# ESP-WROOM32-Breakout_v13.net
KiCad netlist of a schematic drawn in EAGLE
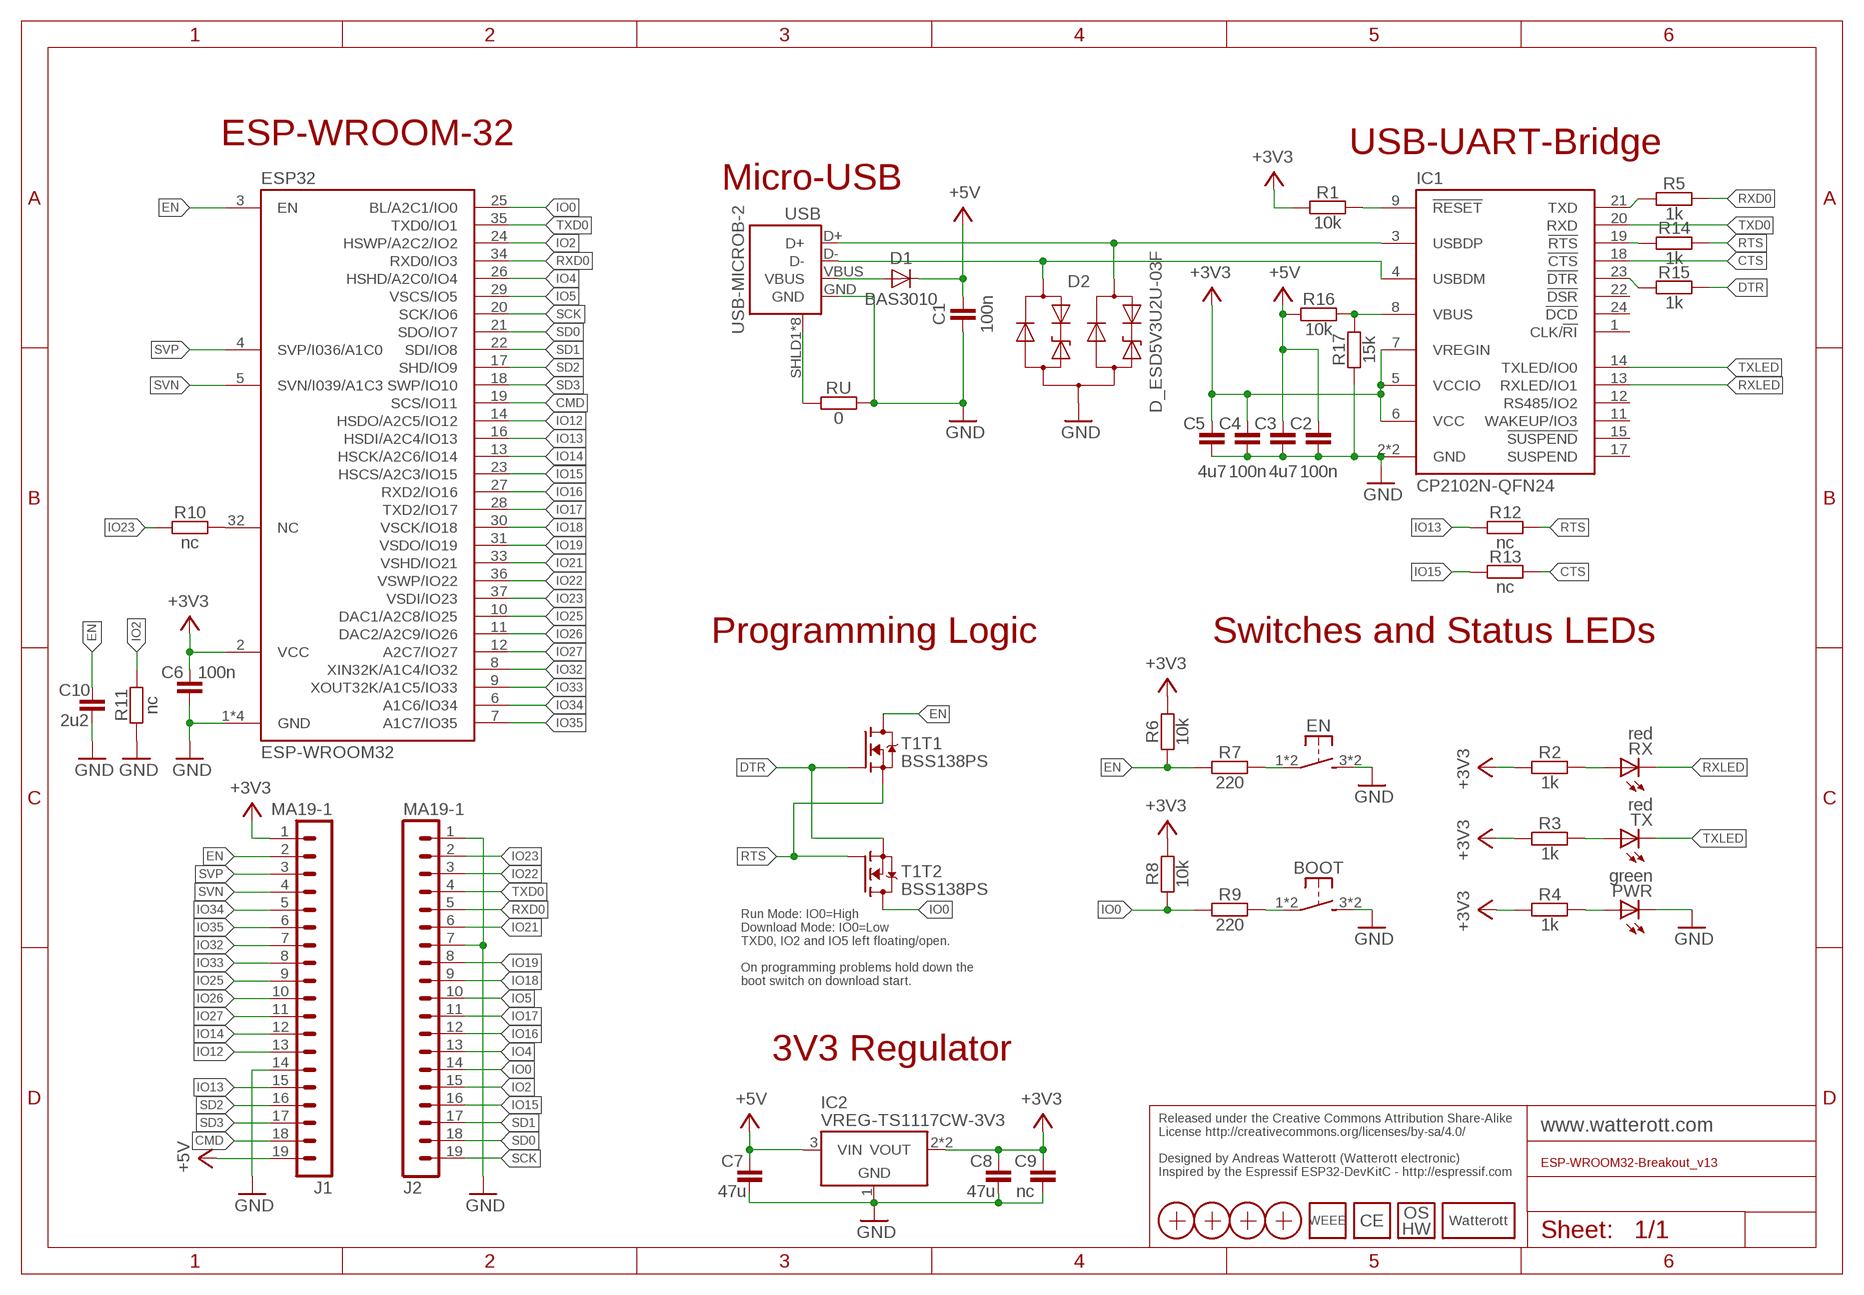
[diagram p0: schematic, sheet 1]

(export (version "E")
  (design (tool "Eeschema 10.0.6"))
  (components
    (comp (ref "BOOT")
      (value "SW-TACTILE-PTS840P")
      (footprint "eagle-import:PTS840P")
      (libsource (lib "eagle-import") (part "SW-TACTILE-PTS840P"))
    )
    (comp (ref "C1")
      (value "100n")
      (footprint "eagle-import:C0402")
      (libsource (lib "eagle-import") (part "CAPACITOR-0402"))
    )
    (comp (ref "C2")
      (value "100n")
      (footprint "eagle-import:C0402")
      (libsource (lib "eagle-import") (part "CAPACITOR-0402"))
    )
    (comp (ref "C3")
      (value "4u7")
      (footprint "eagle-import:C0603")
      (libsource (lib "eagle-import") (part "CAPACITOR-0603"))
    )
    (comp (ref "C4")
      (value "100n")
      (footprint "eagle-import:C0402")
      (libsource (lib "eagle-import") (part "CAPACITOR-0402"))
    )
    (comp (ref "C5")
      (value "4u7")
      (footprint "eagle-import:C0603")
      (libsource (lib "eagle-import") (part "CAPACITOR-0603"))
    )
    (comp (ref "C6")
      (value "100n")
      (footprint "eagle-import:C0402")
      (libsource (lib "eagle-import") (part "CAPACITOR-0402"))
    )
    (comp (ref "C7")
      (value "47u")
      (footprint "eagle-import:C1206")
      (libsource (lib "eagle-import") (part "CAPACITOR-1206"))
    )
    (comp (ref "C8")
      (value "47u")
      (footprint "eagle-import:C1206")
      (libsource (lib "eagle-import") (part "CAPACITOR-1206"))
    )
    (comp (ref "C9")
      (value "nc")
      (footprint "eagle-import:C1206")
      (libsource (lib "eagle-import") (part "CAPACITOR-1206"))
    )
    (comp (ref "C10")
      (value "2u2")
      (footprint "eagle-import:C0402")
      (libsource (lib "eagle-import") (part "CAPACITOR-0402"))
    )
    (comp (ref "D1")
      (value "BAS3010")
      (footprint "eagle-import:SOD323")
      (libsource (lib "eagle-import") (part "DIODE-SOD323"))
    )
    (comp (ref "D2")
      (value "D_ESD5V3U2U-03F")
      (footprint "eagle-import:SOT723")
      (libsource (lib "eagle-import") (part "D_ESD5V3U2U-03F"))
    )
    (comp (ref "EN")
      (value "SW-TACTILE-PTS840P")
      (footprint "eagle-import:PTS840P")
      (libsource (lib "eagle-import") (part "SW-TACTILE-PTS840P"))
    )
    (comp (ref "ESP32")
      (value "ESP-WROOM32")
      (footprint "eagle-import:ESP-WROOM32")
      (libsource (lib "eagle-import") (part "ESP-WROOM32"))
    )
    (comp (ref "IC1")
      (value "CP2102N-QFN24")
      (footprint "eagle-import:QFN24-PAD")
      (libsource (lib "eagle-import") (part "CP2102N-QFN24"))
    )
    (comp (ref "IC2")
      (value "VREG-TS1117CW-3V3")
      (footprint "eagle-import:SOT223")
      (libsource (lib "eagle-import") (part "VREG-TS1117CW-3V3"))
    )
    (comp (ref "J1")
      (value "MA19-1")
      (footprint "eagle-import:MA19-1")
      (libsource (lib "eagle-import") (part "MA19-1"))
    )
    (comp (ref "J2")
      (value "MA19-1")
      (footprint "eagle-import:MA19-1")
      (libsource (lib "eagle-import") (part "MA19-1"))
    )
    (comp (ref "LOGO1")
      (value "LOGO_SPARK-4")
      (footprint "eagle-import:SPARK_4MM")
      (libsource (lib "eagle-import") (part "LOGO_SPARK-4"))
    )
    (comp (ref "LOGO2")
      (value "LOGO_OSHW-2")
      (footprint "eagle-import:OSHW_2MM")
      (libsource (lib "eagle-import") (part "LOGO_OSHW-2"))
    )
    (comp (ref "LOGO3")
      (value "LOGO_CE-2")
      (footprint "eagle-import:CE_2MM")
      (libsource (lib "eagle-import") (part "LOGO_CE-2"))
    )
    (comp (ref "LOGO4")
      (value "LOGO_WEEE-4")
      (footprint "eagle-import:WEEE_4MM")
      (libsource (lib "eagle-import") (part "LOGO_WEEE-4"))
    )
    (comp (ref "PWR")
      (value "green")
      (footprint "eagle-import:C0603")
      (libsource (lib "eagle-import") (part "LED-0603"))
    )
    (comp (ref "R1")
      (value "10k")
      (footprint "eagle-import:C0402")
      (libsource (lib "eagle-import") (part "RESISTOR-0402"))
    )
    (comp (ref "R2")
      (value "1k")
      (footprint "eagle-import:C0402")
      (libsource (lib "eagle-import") (part "RESISTOR-0402"))
    )
    (comp (ref "R3")
      (value "1k")
      (footprint "eagle-import:C0402")
      (libsource (lib "eagle-import") (part "RESISTOR-0402"))
    )
    (comp (ref "R4")
      (value "1k")
      (footprint "eagle-import:C0402")
      (libsource (lib "eagle-import") (part "RESISTOR-0402"))
    )
    (comp (ref "R5")
      (value "1k")
      (footprint "eagle-import:C0402")
      (libsource (lib "eagle-import") (part "RESISTOR-0402"))
    )
    (comp (ref "R6")
      (value "10k")
      (footprint "eagle-import:C0402")
      (libsource (lib "eagle-import") (part "RESISTOR-0402"))
    )
    (comp (ref "R7")
      (value "220")
      (footprint "eagle-import:C0402")
      (libsource (lib "eagle-import") (part "RESISTOR-0402"))
    )
    (comp (ref "R8")
      (value "10k")
      (footprint "eagle-import:C0402")
      (libsource (lib "eagle-import") (part "RESISTOR-0402"))
    )
    (comp (ref "R9")
      (value "220")
      (footprint "eagle-import:C0402")
      (libsource (lib "eagle-import") (part "RESISTOR-0402"))
    )
    (comp (ref "R10")
      (value "nc")
      (footprint "eagle-import:C0402")
      (libsource (lib "eagle-import") (part "RESISTOR-0402"))
    )
    (comp (ref "R11")
      (value "nc")
      (footprint "eagle-import:C0402")
      (libsource (lib "eagle-import") (part "RESISTOR-0402"))
    )
    (comp (ref "R12")
      (value "nc")
      (footprint "eagle-import:C0402")
      (libsource (lib "eagle-import") (part "RESISTOR-0402"))
    )
    (comp (ref "R13")
      (value "nc")
      (footprint "eagle-import:C0402")
      (libsource (lib "eagle-import") (part "RESISTOR-0402"))
    )
    (comp (ref "R14")
      (value "1k")
      (footprint "eagle-import:C0402")
      (libsource (lib "eagle-import") (part "RESISTOR-0402"))
    )
    (comp (ref "R15")
      (value "1k")
      (footprint "eagle-import:C0402")
      (libsource (lib "eagle-import") (part "RESISTOR-0402"))
    )
    (comp (ref "R16")
      (value "10k")
      (footprint "eagle-import:C0402")
      (libsource (lib "eagle-import") (part "RESISTOR-0402"))
    )
    (comp (ref "R17")
      (value "15k")
      (footprint "eagle-import:C0402")
      (libsource (lib "eagle-import") (part "RESISTOR-0402"))
    )
    (comp (ref "RU")
      (value "0")
      (footprint "eagle-import:C0402")
      (libsource (lib "eagle-import") (part "RESISTOR-0402"))
    )
    (comp (ref "RX")
      (value "red")
      (footprint "eagle-import:C0603")
      (libsource (lib "eagle-import") (part "LED-0603"))
    )
    (comp (ref "T1")
      (value "BSS138PS")
      (footprint "eagle-import:SOT363")
      (libsource (lib "eagle-import") (part "BSS138PS"))
    )
    (comp (ref "TX")
      (value "red")
      (footprint "eagle-import:C0603")
      (libsource (lib "eagle-import") (part "LED-0603"))
    )
    (comp (ref "USB")
      (value "USB-MICROB-2")
      (footprint "eagle-import:USB-MICROB-10118194")
      (libsource (lib "eagle-import") (part "USB-MICROB-2"))
    )
    (comp (ref "X1")
      (value "PASSER-07")
      (footprint "eagle-import:PASSER_07MM")
      (libsource (lib "eagle-import") (part "PASSER-07"))
    )
    (comp (ref "X2")
      (value "PASSER-07")
      (footprint "eagle-import:PASSER_07MM")
      (libsource (lib "eagle-import") (part "PASSER-07"))
    )
    (comp (ref "X3")
      (value "PASSER-07")
      (footprint "eagle-import:PASSER_07MM")
      (libsource (lib "eagle-import") (part "PASSER-07"))
    )
    (comp (ref "X4")
      (value "PASSER-07")
      (footprint "eagle-import:PASSER_07MM")
      (libsource (lib "eagle-import") (part "PASSER-07"))
    )
  )
  (nets
    (net (code "1") (name "+3V3") (class "Default")
      (node (ref "C4") (pin "2") (pinfunction "2_2") (pintype "passive"))
      (node (ref "C5") (pin "2") (pinfunction "2_2") (pintype "passive"))
      (node (ref "C6") (pin "2") (pinfunction "2_2") (pintype "passive"))
      (node (ref "C8") (pin "2") (pinfunction "2_2") (pintype "passive"))
      (node (ref "C9") (pin "2") (pinfunction "2_2") (pintype "passive"))
      (node (ref "ESP32") (pin "2") (pinfunction "VCC_2") (pintype "power_in"))
      (node (ref "IC1") (pin "5") (pinfunction "VCCIO_5") (pintype "power_in"))
      (node (ref "IC1") (pin "6") (pinfunction "VCC_6") (pintype "power_in"))
      (node (ref "IC1") (pin "7") (pinfunction "VREGIN_7") (pintype "power_in"))
      (node (ref "IC2") (pin "2") (pinfunction "VOUT_2") (pintype "power_in"))
      (node (ref "IC2") (pin "4") (pinfunction "VOUT_4") (pintype "power_in"))
      (node (ref "J1") (pin "1") (pinfunction "1_1") (pintype "passive"))
      (node (ref "R1") (pin "1") (pinfunction "1_1") (pintype "passive"))
      (node (ref "R2") (pin "1") (pinfunction "1_1") (pintype "passive"))
      (node (ref "R3") (pin "1") (pinfunction "1_1") (pintype "passive"))
      (node (ref "R4") (pin "1") (pinfunction "1_1") (pintype "passive"))
      (node (ref "R6") (pin "2") (pinfunction "2_2") (pintype "passive"))
      (node (ref "R8") (pin "2") (pinfunction "2_2") (pintype "passive"))
    )
    (net (code "2") (name "+5V") (class "Default")
      (node (ref "C1") (pin "2") (pinfunction "2_2") (pintype "passive"))
      (node (ref "C2") (pin "2") (pinfunction "2_2") (pintype "passive"))
      (node (ref "C3") (pin "2") (pinfunction "2_2") (pintype "passive"))
      (node (ref "C7") (pin "2") (pinfunction "2_2") (pintype "passive"))
      (node (ref "D1") (pin "C") (pinfunction "C_C") (pintype "passive"))
      (node (ref "IC2") (pin "3") (pinfunction "VIN_3") (pintype "power_in"))
      (node (ref "J1") (pin "19") (pinfunction "19_19") (pintype "passive"))
      (node (ref "R16") (pin "1") (pinfunction "1_1") (pintype "passive"))
    )
    (net (code "3") (name "CMD") (class "Default")
      (node (ref "ESP32") (pin "19") (pinfunction "SCS/IO11_19") (pintype "bidirectional"))
      (node (ref "J1") (pin "18") (pinfunction "18_18") (pintype "passive"))
    )
    (net (code "4") (name "CTS") (class "Default")
      (node (ref "IC1") (pin "18") (pinfunction "~{CTS}_18") (pintype "bidirectional"))
      (node (ref "R13") (pin "2") (pinfunction "2_2") (pintype "passive"))
    )
    (net (code "5") (name "DTR") (class "Default")
      (node (ref "R15") (pin "2") (pinfunction "2_2") (pintype "passive"))
      (node (ref "T1") (pin "2") (pinfunction "G_2") (pintype "passive"))
      (node (ref "T1") (pin "4") (pinfunction "S_4") (pintype "passive"))
    )
    (net (code "6") (name "EN") (class "Default")
      (node (ref "C10") (pin "2") (pinfunction "2_2") (pintype "passive"))
      (node (ref "ESP32") (pin "3") (pinfunction "EN_3") (pintype "bidirectional"))
      (node (ref "J1") (pin "2") (pinfunction "2_2") (pintype "passive"))
      (node (ref "R6") (pin "1") (pinfunction "1_1") (pintype "passive"))
      (node (ref "R7") (pin "1") (pinfunction "1_1") (pintype "passive"))
      (node (ref "T1") (pin "6") (pinfunction "D_6") (pintype "passive"))
    )
    (net (code "7") (name "GND") (class "Default")
      (node (ref "BOOT") (pin "3") (pinfunction "S1_3") (pintype "passive"))
      (node (ref "BOOT") (pin "4") (pinfunction "S1_4") (pintype "passive"))
      (node (ref "C1") (pin "1") (pinfunction "1_1") (pintype "passive"))
      (node (ref "C10") (pin "1") (pinfunction "1_1") (pintype "passive"))
      (node (ref "C2") (pin "1") (pinfunction "1_1") (pintype "passive"))
      (node (ref "C3") (pin "1") (pinfunction "1_1") (pintype "passive"))
      (node (ref "C4") (pin "1") (pinfunction "1_1") (pintype "passive"))
      (node (ref "C5") (pin "1") (pinfunction "1_1") (pintype "passive"))
      (node (ref "C6") (pin "1") (pinfunction "1_1") (pintype "passive"))
      (node (ref "C7") (pin "1") (pinfunction "1_1") (pintype "passive"))
      (node (ref "C8") (pin "1") (pinfunction "1_1") (pintype "passive"))
      (node (ref "C9") (pin "1") (pinfunction "1_1") (pintype "passive"))
      (node (ref "D2") (pin "3") (pinfunction "A_3") (pintype "passive"))
      (node (ref "EN") (pin "3") (pinfunction "S1_3") (pintype "passive"))
      (node (ref "EN") (pin "4") (pinfunction "S1_4") (pintype "passive"))
      (node (ref "ESP32") (pin "1") (pinfunction "GND_1") (pintype "power_in"))
      (node (ref "ESP32") (pin "15") (pinfunction "GND_15") (pintype "power_in"))
      (node (ref "ESP32") (pin "38") (pinfunction "GND_38") (pintype "power_in"))
      (node (ref "ESP32") (pin "TP") (pinfunction "GND_TP") (pintype "power_in"))
      (node (ref "IC1") (pin "2") (pinfunction "GND_2") (pintype "power_in"))
      (node (ref "IC1") (pin "TP") (pinfunction "GND_TP") (pintype "power_in"))
      (node (ref "IC2") (pin "1") (pinfunction "GND_1") (pintype "power_in"))
      (node (ref "J1") (pin "14") (pinfunction "14_14") (pintype "passive"))
      (node (ref "J2") (pin "1") (pinfunction "1_1") (pintype "passive"))
      (node (ref "J2") (pin "7") (pinfunction "7_7") (pintype "passive"))
      (node (ref "PWR") (pin "C") (pinfunction "C_C") (pintype "passive"))
      (node (ref "R11") (pin "1") (pinfunction "1_1") (pintype "passive"))
      (node (ref "R17") (pin "1") (pinfunction "1_1") (pintype "passive"))
      (node (ref "RU") (pin "2") (pinfunction "2_2") (pintype "passive"))
      (node (ref "USB") (pin "GND") (pinfunction "GND_GND") (pintype "power_in"))
    )
    (net (code "8") (name "IO0") (class "Default")
      (node (ref "ESP32") (pin "25") (pinfunction "BL/A2C1/IO0_25") (pintype "bidirectional"))
      (node (ref "J2") (pin "14") (pinfunction "14_14") (pintype "passive"))
      (node (ref "R8") (pin "1") (pinfunction "1_1") (pintype "passive"))
      (node (ref "R9") (pin "1") (pinfunction "1_1") (pintype "passive"))
      (node (ref "T1") (pin "3") (pinfunction "D_3") (pintype "passive"))
    )
    (net (code "9") (name "IO2") (class "Default")
      (node (ref "ESP32") (pin "24") (pinfunction "HSWP/A2C2/IO2_24") (pintype "bidirectional"))
      (node (ref "J2") (pin "15") (pinfunction "15_15") (pintype "passive"))
      (node (ref "R11") (pin "2") (pinfunction "2_2") (pintype "passive"))
    )
    (net (code "10") (name "IO4") (class "Default")
      (node (ref "ESP32") (pin "26") (pinfunction "HSHD/A2C0/IO4_26") (pintype "bidirectional"))
      (node (ref "J2") (pin "13") (pinfunction "13_13") (pintype "passive"))
    )
    (net (code "11") (name "IO5") (class "Default")
      (node (ref "ESP32") (pin "29") (pinfunction "VSCS/IO5_29") (pintype "bidirectional"))
      (node (ref "J2") (pin "10") (pinfunction "10_10") (pintype "passive"))
    )
    (net (code "12") (name "IO12") (class "Default")
      (node (ref "ESP32") (pin "14") (pinfunction "HSDO/A2C5/IO12_14") (pintype "bidirectional"))
      (node (ref "J1") (pin "13") (pinfunction "13_13") (pintype "passive"))
    )
    (net (code "13") (name "IO13") (class "Default")
      (node (ref "ESP32") (pin "16") (pinfunction "HSDI/A2C4/IO13_16") (pintype "bidirectional"))
      (node (ref "J1") (pin "15") (pinfunction "15_15") (pintype "passive"))
      (node (ref "R12") (pin "1") (pinfunction "1_1") (pintype "passive"))
    )
    (net (code "14") (name "IO14") (class "Default")
      (node (ref "ESP32") (pin "13") (pinfunction "HSCK/A2C6/IO14_13") (pintype "bidirectional"))
      (node (ref "J1") (pin "12") (pinfunction "12_12") (pintype "passive"))
    )
    (net (code "15") (name "IO15") (class "Default")
      (node (ref "ESP32") (pin "23") (pinfunction "HSCS/A2C3/IO15_23") (pintype "bidirectional"))
      (node (ref "J2") (pin "16") (pinfunction "16_16") (pintype "passive"))
      (node (ref "R13") (pin "1") (pinfunction "1_1") (pintype "passive"))
    )
    (net (code "16") (name "IO16") (class "Default")
      (node (ref "ESP32") (pin "27") (pinfunction "RXD2/IO16_27") (pintype "bidirectional"))
      (node (ref "J2") (pin "12") (pinfunction "12_12") (pintype "passive"))
    )
    (net (code "17") (name "IO17") (class "Default")
      (node (ref "ESP32") (pin "28") (pinfunction "TXD2/IO17_28") (pintype "bidirectional"))
      (node (ref "J2") (pin "11") (pinfunction "11_11") (pintype "passive"))
    )
    (net (code "18") (name "IO18") (class "Default")
      (node (ref "ESP32") (pin "30") (pinfunction "VSCK/IO18_30") (pintype "bidirectional"))
      (node (ref "J2") (pin "9") (pinfunction "9_9") (pintype "passive"))
    )
    (net (code "19") (name "IO19") (class "Default")
      (node (ref "ESP32") (pin "31") (pinfunction "VSDO/IO19_31") (pintype "bidirectional"))
      (node (ref "J2") (pin "8") (pinfunction "8_8") (pintype "passive"))
    )
    (net (code "20") (name "IO21") (class "Default")
      (node (ref "ESP32") (pin "33") (pinfunction "VSHD/IO21_33") (pintype "bidirectional"))
      (node (ref "J2") (pin "6") (pinfunction "6_6") (pintype "passive"))
    )
    (net (code "21") (name "IO22") (class "Default")
      (node (ref "ESP32") (pin "36") (pinfunction "VSWP/IO22_36") (pintype "bidirectional"))
      (node (ref "J2") (pin "3") (pinfunction "3_3") (pintype "passive"))
    )
    (net (code "22") (name "IO23") (class "Default")
      (node (ref "ESP32") (pin "37") (pinfunction "VSDI/IO23_37") (pintype "bidirectional"))
      (node (ref "J2") (pin "2") (pinfunction "2_2") (pintype "passive"))
      (node (ref "R10") (pin "1") (pinfunction "1_1") (pintype "passive"))
    )
    (net (code "23") (name "IO25") (class "Default")
      (node (ref "ESP32") (pin "10") (pinfunction "DAC1/A2C8/IO25_10") (pintype "bidirectional"))
      (node (ref "J1") (pin "9") (pinfunction "9_9") (pintype "passive"))
    )
    (net (code "24") (name "IO26") (class "Default")
      (node (ref "ESP32") (pin "11") (pinfunction "DAC2/A2C9/IO26_11") (pintype "bidirectional"))
      (node (ref "J1") (pin "10") (pinfunction "10_10") (pintype "passive"))
    )
    (net (code "25") (name "IO27") (class "Default")
      (node (ref "ESP32") (pin "12") (pinfunction "A2C7/IO27_12") (pintype "bidirectional"))
      (node (ref "J1") (pin "11") (pinfunction "11_11") (pintype "passive"))
    )
    (net (code "26") (name "IO32") (class "Default")
      (node (ref "ESP32") (pin "8") (pinfunction "XIN32K/A1C4/IO32_8") (pintype "bidirectional"))
      (node (ref "J1") (pin "7") (pinfunction "7_7") (pintype "passive"))
    )
    (net (code "27") (name "IO33") (class "Default")
      (node (ref "ESP32") (pin "9") (pinfunction "XOUT32K/A1C5/IO33_9") (pintype "bidirectional"))
      (node (ref "J1") (pin "8") (pinfunction "8_8") (pintype "passive"))
    )
    (net (code "28") (name "IO34") (class "Default")
      (node (ref "ESP32") (pin "6") (pinfunction "A1C6/IO34_6") (pintype "bidirectional"))
      (node (ref "J1") (pin "5") (pinfunction "5_5") (pintype "passive"))
    )
    (net (code "29") (name "IO35") (class "Default")
      (node (ref "ESP32") (pin "7") (pinfunction "A1C7/IO35_7") (pintype "bidirectional"))
      (node (ref "J1") (pin "6") (pinfunction "6_6") (pintype "passive"))
    )
    (net (code "30") (name "Net-(BOOT-P1-Pad1)") (class "Default")
      (node (ref "BOOT") (pin "1") (pinfunction "P1_1") (pintype "passive"))
      (node (ref "BOOT") (pin "2") (pinfunction "P1_2") (pintype "passive"))
      (node (ref "R9") (pin "2") (pinfunction "2_2") (pintype "passive"))
    )
    (net (code "31") (name "Net-(D1-PadA)") (class "Default")
      (node (ref "D1") (pin "A") (pinfunction "A_A") (pintype "passive"))
      (node (ref "USB") (pin "VBUS") (pinfunction "VBUS_VBUS") (pintype "power_in"))
    )
    (net (code "32") (name "Net-(D2-C1)") (class "Default")
      (node (ref "D2") (pin "1") (pinfunction "C1_1") (pintype "passive"))
      (node (ref "IC1") (pin "4") (pinfunction "USBDM_4") (pintype "bidirectional"))
      (node (ref "USB") (pin "D-") (pinfunction "D-_D-") (pintype "bidirectional"))
    )
    (net (code "33") (name "Net-(D2-C2)") (class "Default")
      (node (ref "D2") (pin "2") (pinfunction "C2_2") (pintype "passive"))
      (node (ref "IC1") (pin "3") (pinfunction "USBDP_3") (pintype "bidirectional"))
      (node (ref "USB") (pin "D+") (pinfunction "D+_D+") (pintype "bidirectional"))
    )
    (net (code "34") (name "Net-(EN-P1-Pad1)") (class "Default")
      (node (ref "EN") (pin "1") (pinfunction "P1_1") (pintype "passive"))
      (node (ref "EN") (pin "2") (pinfunction "P1_2") (pintype "passive"))
      (node (ref "R7") (pin "2") (pinfunction "2_2") (pintype "passive"))
    )
    (net (code "35") (name "Net-(ESP32-NC)") (class "Default")
      (node (ref "ESP32") (pin "32") (pinfunction "NC_32") (pintype "bidirectional"))
      (node (ref "R10") (pin "2") (pinfunction "2_2") (pintype "passive"))
    )
    (net (code "36") (name "Net-(IC1-TXD)") (class "Default")
      (node (ref "IC1") (pin "21") (pinfunction "TXD_21") (pintype "bidirectional"))
      (node (ref "R5") (pin "1") (pinfunction "1_1") (pintype "passive"))
    )
    (net (code "37") (name "Net-(IC1-VBUS)") (class "Default")
      (node (ref "IC1") (pin "8") (pinfunction "VBUS_8") (pintype "power_in"))
      (node (ref "R16") (pin "2") (pinfunction "2_2") (pintype "passive"))
      (node (ref "R17") (pin "2") (pinfunction "2_2") (pintype "passive"))
    )
    (net (code "38") (name "Net-(IC1-~{DTR})") (class "Default")
      (node (ref "IC1") (pin "23") (pinfunction "~{DTR}_23") (pintype "bidirectional"))
      (node (ref "R15") (pin "1") (pinfunction "1_1") (pintype "passive"))
    )
    (net (code "39") (name "Net-(IC1-~{RESET})") (class "Default")
      (node (ref "IC1") (pin "9") (pinfunction "~{RESET}_9") (pintype "bidirectional"))
      (node (ref "R1") (pin "2") (pinfunction "2_2") (pintype "passive"))
    )
    (net (code "40") (name "Net-(IC1-~{RTS})") (class "Default")
      (node (ref "IC1") (pin "19") (pinfunction "~{RTS}_19") (pintype "bidirectional"))
      (node (ref "R14") (pin "1") (pinfunction "1_1") (pintype "passive"))
    )
    (net (code "41") (name "Net-(PWR-PadA)") (class "Default")
      (node (ref "PWR") (pin "A") (pinfunction "A_A") (pintype "passive"))
      (node (ref "R4") (pin "2") (pinfunction "2_2") (pintype "passive"))
    )
    (net (code "42") (name "Net-(R2-Pad2)") (class "Default")
      (node (ref "R2") (pin "2") (pinfunction "2_2") (pintype "passive"))
      (node (ref "RX") (pin "A") (pinfunction "A_A") (pintype "passive"))
    )
    (net (code "43") (name "Net-(R3-Pad2)") (class "Default")
      (node (ref "R3") (pin "2") (pinfunction "2_2") (pintype "passive"))
      (node (ref "TX") (pin "A") (pinfunction "A_A") (pintype "passive"))
    )
    (net (code "44") (name "Net-(RU-Pad1)") (class "Default")
      (node (ref "RU") (pin "1") (pinfunction "1_1") (pintype "passive"))
      (node (ref "USB") (pin "SHLD1") (pinfunction "SHIELD_SHLD1") (pintype "passive"))
      (node (ref "USB") (pin "SHLD2") (pinfunction "SHIELD_SHLD2") (pintype "passive"))
      (node (ref "USB") (pin "SHLD3") (pinfunction "SHIELD_SHLD3") (pintype "passive"))
      (node (ref "USB") (pin "SHLD4") (pinfunction "SHIELD_SHLD4") (pintype "passive"))
      (node (ref "USB") (pin "SHLD5") (pinfunction "SHIELD_SHLD5") (pintype "passive"))
      (node (ref "USB") (pin "SHLD6") (pinfunction "SHIELD_SHLD6") (pintype "passive"))
      (node (ref "USB") (pin "SHLD7") (pinfunction "SHIELD_SHLD7") (pintype "passive"))
      (node (ref "USB") (pin "SHLD8") (pinfunction "SHIELD_SHLD8") (pintype "passive"))
    )
    (net (code "45") (name "RTS") (class "Default")
      (node (ref "R12") (pin "2") (pinfunction "2_2") (pintype "passive"))
      (node (ref "R14") (pin "2") (pinfunction "2_2") (pintype "passive"))
      (node (ref "T1") (pin "1") (pinfunction "S_1") (pintype "passive"))
      (node (ref "T1") (pin "5") (pinfunction "G_5") (pintype "passive"))
    )
    (net (code "46") (name "RXD0") (class "Default")
      (node (ref "ESP32") (pin "34") (pinfunction "RXD0/IO3_34") (pintype "bidirectional"))
      (node (ref "J2") (pin "5") (pinfunction "5_5") (pintype "passive"))
      (node (ref "R5") (pin "2") (pinfunction "2_2") (pintype "passive"))
    )
    (net (code "47") (name "RXLED") (class "Default")
      (node (ref "IC1") (pin "13") (pinfunction "RXLED/IO1_13") (pintype "bidirectional"))
      (node (ref "RX") (pin "C") (pinfunction "C_C") (pintype "passive"))
    )
    (net (code "48") (name "SCK") (class "Default")
      (node (ref "ESP32") (pin "20") (pinfunction "SCK/IO6_20") (pintype "bidirectional"))
      (node (ref "J2") (pin "19") (pinfunction "19_19") (pintype "passive"))
    )
    (net (code "49") (name "SD0") (class "Default")
      (node (ref "ESP32") (pin "21") (pinfunction "SDO/IO7_21") (pintype "bidirectional"))
      (node (ref "J2") (pin "18") (pinfunction "18_18") (pintype "passive"))
    )
    (net (code "50") (name "SD1") (class "Default")
      (node (ref "ESP32") (pin "22") (pinfunction "SDI/IO8_22") (pintype "bidirectional"))
      (node (ref "J2") (pin "17") (pinfunction "17_17") (pintype "passive"))
    )
    (net (code "51") (name "SD2") (class "Default")
      (node (ref "ESP32") (pin "17") (pinfunction "SHD/IO9_17") (pintype "bidirectional"))
      (node (ref "J1") (pin "16") (pinfunction "16_16") (pintype "passive"))
    )
    (net (code "52") (name "SD3") (class "Default")
      (node (ref "ESP32") (pin "18") (pinfunction "SWP/IO10_18") (pintype "bidirectional"))
      (node (ref "J1") (pin "17") (pinfunction "17_17") (pintype "passive"))
    )
    (net (code "53") (name "SVN") (class "Default")
      (node (ref "ESP32") (pin "5") (pinfunction "SVN/I039/A1C3_5") (pintype "bidirectional"))
      (node (ref "J1") (pin "4") (pinfunction "4_4") (pintype "passive"))
    )
    (net (code "54") (name "SVP") (class "Default")
      (node (ref "ESP32") (pin "4") (pinfunction "SVP/I036/A1C0_4") (pintype "bidirectional"))
      (node (ref "J1") (pin "3") (pinfunction "3_3") (pintype "passive"))
    )
    (net (code "55") (name "TXD0") (class "Default")
      (node (ref "ESP32") (pin "35") (pinfunction "TXD0/IO1_35") (pintype "bidirectional"))
      (node (ref "IC1") (pin "20") (pinfunction "RXD_20") (pintype "bidirectional"))
      (node (ref "J2") (pin "4") (pinfunction "4_4") (pintype "passive"))
    )
    (net (code "56") (name "TXLED") (class "Default")
      (node (ref "IC1") (pin "14") (pinfunction "TXLED/IO0_14") (pintype "bidirectional"))
      (node (ref "TX") (pin "C") (pinfunction "C_C") (pintype "passive"))
    )
    (net (code "57") (name "unconnected-(IC1-CLK{slash}~{RI}-Pad1)") (class "Default")
      (node (ref "IC1") (pin "1") (pinfunction "CLK/~{RI}_1") (pintype "bidirectional"))
    )
    (net (code "58") (name "unconnected-(IC1-RS485{slash}IO2-Pad12)") (class "Default")
      (node (ref "IC1") (pin "12") (pinfunction "RS485/IO2_12") (pintype "bidirectional"))
    )
    (net (code "59") (name "unconnected-(IC1-SUSPEND-Pad17)") (class "Default")
      (node (ref "IC1") (pin "17") (pinfunction "SUSPEND_17") (pintype "bidirectional"))
    )
    (net (code "60") (name "unconnected-(IC1-WAKEUP{slash}IO3-Pad11)") (class "Default")
      (node (ref "IC1") (pin "11") (pinfunction "WAKEUP/IO3_11") (pintype "bidirectional"))
    )
    (net (code "61") (name "unconnected-(IC1-~{DCD}-Pad24)") (class "Default")
      (node (ref "IC1") (pin "24") (pinfunction "~{DCD}_24") (pintype "bidirectional"))
    )
    (net (code "62") (name "unconnected-(IC1-~{DSR}-Pad22)") (class "Default")
      (node (ref "IC1") (pin "22") (pinfunction "~{DSR}_22") (pintype "bidirectional"))
    )
    (net (code "63") (name "unconnected-(IC1-~{SUSPEND}-Pad15)") (class "Default")
      (node (ref "IC1") (pin "15") (pinfunction "~{SUSPEND}_15") (pintype "bidirectional"))
    )
  )
)
